# BananaSchplit-Mini-USBCPD-Schematic.net
KiCad netlist of a schematic drawn in Altium Designer
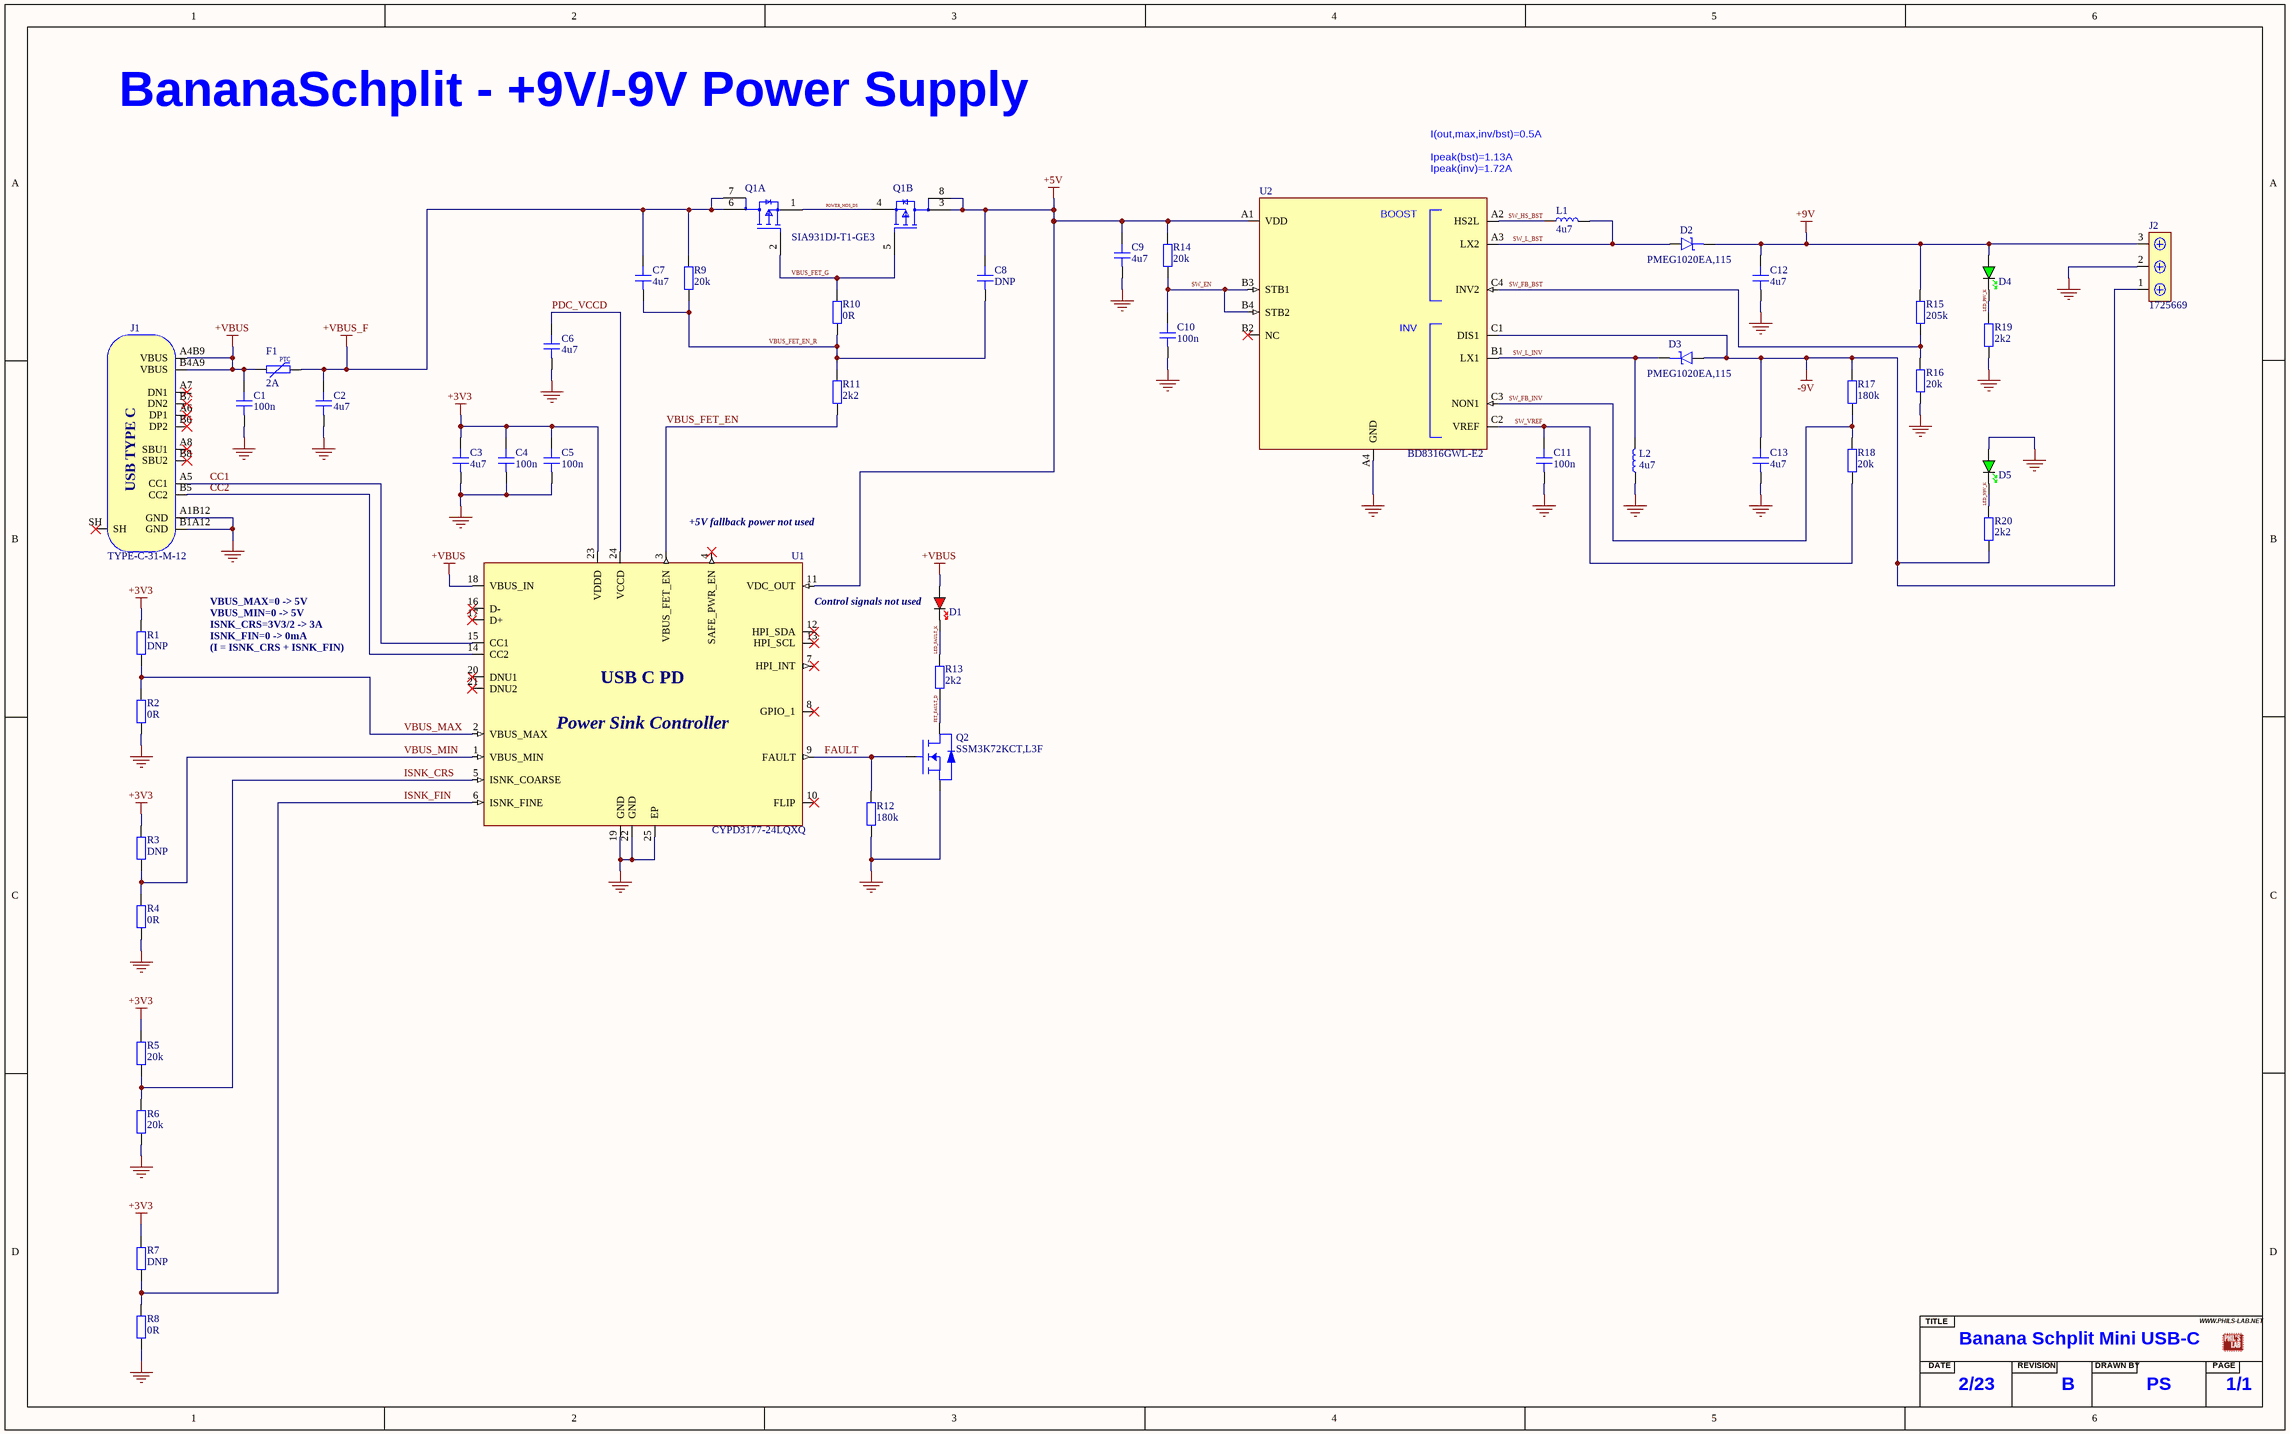
[diagram p0: BananaSchplit-Mini-USBCPD-Schematic.SchDoc]

(export (version "E")
  (design (tool "Eeschema 10.0.6"))
  (components
    (comp (ref "C1")
      (value "100n")
      (footprint "CAP_0402")
      (description "Capacitor SMD 0402 25V")
      (fields
        (field (name "MANUFACTURER") "Murata")
        (field (name "MANUFACTURER PART NUMBER") "GRM155R71H104KE14D")
      )
      (libsource (lib "Schematic-Lib-PhilsLab") (part "CAP_0402_25V"))
    )
    (comp (ref "C2")
      (value "4u7")
      (footprint "CAP_0603")
      (description "Capacitor SMD 0603 25V")
      (fields
        (field (name "MANUFACTURER") "Murata")
        (field (name "MANUFACTURER PART NUMBER") "GRT188R61E475ME13D")
      )
      (libsource (lib "Schematic-Lib-PhilsLab") (part "CAP_0603_25V"))
    )
    (comp (ref "C3")
      (value "4u7")
      (footprint "CAP_0603")
      (description "Capacitor SMD 0603 25V")
      (fields
        (field (name "MANUFACTURER") "Murata")
        (field (name "MANUFACTURER PART NUMBER") "GRT188R61E475ME13D")
      )
      (libsource (lib "Schematic-Lib-PhilsLab") (part "CAP_0603_25V"))
    )
    (comp (ref "C4")
      (value "100n")
      (footprint "CAP_0402")
      (description "Capacitor SMD 0402 25V")
      (fields
        (field (name "MANUFACTURER") "Murata")
        (field (name "MANUFACTURER PART NUMBER") "GRM155R71H104KE14D")
      )
      (libsource (lib "Schematic-Lib-PhilsLab") (part "CAP_0402_25V"))
    )
    (comp (ref "C5")
      (value "100n")
      (footprint "CAP_0402")
      (description "Capacitor SMD 0402 25V")
      (fields
        (field (name "MANUFACTURER") "Murata")
        (field (name "MANUFACTURER PART NUMBER") "GRM155R71H104KE14D")
      )
      (libsource (lib "Schematic-Lib-PhilsLab") (part "CAP_0402_25V"))
    )
    (comp (ref "C6")
      (value "4u7")
      (footprint "CAP_0603")
      (description "Capacitor SMD 0603 25V")
      (fields
        (field (name "MANUFACTURER") "Murata")
        (field (name "MANUFACTURER PART NUMBER") "GRT188R61E475ME13D")
      )
      (libsource (lib "Schematic-Lib-PhilsLab") (part "CAP_0603_25V"))
    )
    (comp (ref "C7")
      (value "4u7")
      (footprint "CAP_0603")
      (description "Capacitor SMD 0603 25V")
      (fields
        (field (name "MANUFACTURER") "Murata")
        (field (name "MANUFACTURER PART NUMBER") "GRT188R61E475ME13D")
      )
      (libsource (lib "Schematic-Lib-PhilsLab") (part "CAP_0603_25V"))
    )
    (comp (ref "C8")
      (value "DNP")
      (footprint "CAP_0402")
      (description "Capacitor SMD 0402 25V")
      (libsource (lib "Schematic-Lib-PhilsLab") (part "CAP_0402_25V"))
    )
    (comp (ref "C9")
      (value "4u7")
      (footprint "CAP_0603")
      (description "Capacitor SMD 0603 25V")
      (fields
        (field (name "MANUFACTURER") "Murata")
        (field (name "MANUFACTURER PART NUMBER") "GRT188R61E475ME13D")
      )
      (libsource (lib "Schematic-Lib-PhilsLab") (part "CAP_0603_25V"))
    )
    (comp (ref "C10")
      (value "100n")
      (footprint "CAP_0402")
      (description "Capacitor SMD 0402 25V")
      (fields
        (field (name "MANUFACTURER") "Murata")
        (field (name "MANUFACTURER PART NUMBER") "GRM155R71H104KE14D")
      )
      (libsource (lib "Schematic-Lib-PhilsLab") (part "CAP_0402_25V"))
    )
    (comp (ref "C11")
      (value "100n")
      (footprint "CAP_0402")
      (description "Capacitor SMD 0402 25V")
      (fields
        (field (name "MANUFACTURER") "Murata")
        (field (name "MANUFACTURER PART NUMBER") "GRM155R71H104KE14D")
      )
      (libsource (lib "Schematic-Lib-PhilsLab") (part "CAP_0402_25V"))
    )
    (comp (ref "C12")
      (value "4u7")
      (footprint "CAP_0603")
      (description "Capacitor SMD 0603 25V")
      (fields
        (field (name "MANUFACTURER") "Murata")
        (field (name "MANUFACTURER PART NUMBER") "GRT188R61E475ME13D")
      )
      (libsource (lib "Schematic-Lib-PhilsLab") (part "CAP_0603_25V"))
    )
    (comp (ref "C13")
      (value "4u7")
      (footprint "CAP_0603")
      (description "Capacitor SMD 0603 25V")
      (fields
        (field (name "MANUFACTURER") "Murata")
        (field (name "MANUFACTURER PART NUMBER") "GRT188R61E475ME13D")
      )
      (libsource (lib "Schematic-Lib-PhilsLab") (part "CAP_0603_25V"))
    )
    (comp (ref "D1")
      (value "RED")
      (footprint "LED_0402_RED")
      (description "LED 0402 RED SMD")
      (fields
        (field (name "MANUFACTURER") "Lite-On")
        (field (name "MANUFACTURER PART NUMBER") "LTST-C281KRKT")
      )
      (libsource (lib "Schematic-Lib-PhilsLab") (part "LED_0402_RED"))
    )
    (comp (ref "D2")
      (value "PMEG1020EA,115")
      (footprint "SOD-323")
      (description "Diode Schottky SMD SOD-323")
      (fields (field (name "MANUFACTURER") "Nexperia"))
      (libsource (lib "Schematic-Lib-PhilsLab") (part "D_SCHOTTKY_SOD_323"))
    )
    (comp (ref "D3")
      (value "PMEG1020EA,115")
      (footprint "SOD-323")
      (description "Diode Schottky SMD SOD-323")
      (fields (field (name "MANUFACTURER") "Nexperia"))
      (libsource (lib "Schematic-Lib-PhilsLab") (part "D_SCHOTTKY_SOD_323"))
    )
    (comp (ref "D4")
      (value "GREEN")
      (footprint "LED_0402_GREEN")
      (description "LED 0402 GREEN SMD")
      (fields
        (field (name "MANUFACTURER") "Lite-On")
        (field (name "MANUFACTURER PART NUMBER") "LTST-C281KGKT")
      )
      (libsource (lib "Schematic-Lib-PhilsLab") (part "LED_0402_GREEN"))
    )
    (comp (ref "D5")
      (value "GREEN")
      (footprint "LED_0402_GREEN")
      (description "LED 0402 GREEN SMD")
      (fields
        (field (name "MANUFACTURER") "Lite-On")
        (field (name "MANUFACTURER PART NUMBER") "LTST-C281KGKT")
      )
      (libsource (lib "Schematic-Lib-PhilsLab") (part "LED_0402_GREEN"))
    )
    (comp (ref "F1")
      (value "2A")
      (footprint "FUSE_1206")
      (description "Fuse PPTC SMD 1206")
      (fields (field (name "MANUFACTURER") "Eaton") (field (name "MANUFACTURER PART NUMBER") "PTS12066V200"))
      (libsource (lib "Schematic-Lib-PhilsLab") (part "FUSE_PPTC_1206"))
    )
    (comp (ref "J1")
      (value "TYPE-C-31-M-12")
      (footprint "TYPE-C-31-M-12")
      (description "USB Type C Connector Horizontal SMT")
      (fields (field (name "MANUFACTURER") "Koren Hroparts"))
      (libsource (lib "Schematic-Lib-PhilsLab") (part "TYPE-C-31-M-12"))
    )
    (comp (ref "J2")
      (value "1725669")
      (footprint "1725669")
      (description "Screw Terminal Block 3 Positions 2.54mm")
      (fields (field (name "MANUFACTURER") "Phoenix"))
      (libsource (lib "Schematic-Lib-PhilsLab") (part "1725669"))
    )
    (comp (ref "L1")
      (value "4u7")
      (footprint "SRP3212A")
      (description "Shielded Power Inductor SMD SRP3212A")
      (fields
        (field (name "MANUFACTURER") "Bourns")
        (field (name "MANUFACTURER PART NUMBER") "SRP3212A-4R7M")
      )
      (libsource (lib "Schematic-Lib-PhilsLab") (part "SRP3212A-*"))
    )
    (comp (ref "L2")
      (value "4u7")
      (footprint "SRP3212A")
      (description "Shielded Power Inductor SMD SRP3212A")
      (fields
        (field (name "MANUFACTURER") "Bourns")
        (field (name "MANUFACTURER PART NUMBER") "SRP3212A-4R7M")
      )
      (libsource (lib "Schematic-Lib-PhilsLab") (part "SRP3212A-*"))
    )
    (comp (ref "Q1")
      (value "SIA931DJ-T1-GE3")
      (footprint "FP-C-07431-DUAL-MFG")
      (description "MOSFET 2P-CH 30V 4.5A SC70-6L")
      (fields
        (field (name "MANUFACTURER") "Vishay")
        (field (name "OCTOPART") "https://octopart.com/sia931dj-t1-ge3-vishay-46488088")
      )
      (libsource (lib "Altium Content Vault") (part "000b6ffb9e5d27f556e92134adc54a4"))
    )
    (comp (ref "Q2")
      (value "SSM3K72KCT,L3F")
      (footprint "CST3-SOT-883")
      (description "MOSFET N-Channel Vds=60V Id=400mA Rds(on)=1.05R with ESD Protection")
      (fields (field (name "MANUFACTURER") "Toshiba"))
      (libsource (lib "Schematic-Lib-PhilsLab") (part "SSM3K72KCT,L3F"))
    )
    (comp (ref "R1")
      (value "DNP")
      (footprint "RES_0402")
      (description "Resistor SMD 0402")
      (libsource (lib "Schematic-Lib-PhilsLab") (part "RES_0402"))
    )
    (comp (ref "R2")
      (value "0R")
      (footprint "RES_0402")
      (description "Resistor SMD 0402")
      (fields
        (field (name "MANUFACTURER") "YAGEO")
        (field (name "MANUFACTURER PART NUMBER") "RC0402FR-070RL")
      )
      (libsource (lib "Schematic-Lib-PhilsLab") (part "RES_0402"))
    )
    (comp (ref "R3")
      (value "DNP")
      (footprint "RES_0402")
      (description "Resistor SMD 0402")
      (libsource (lib "Schematic-Lib-PhilsLab") (part "RES_0402"))
    )
    (comp (ref "R4")
      (value "0R")
      (footprint "RES_0402")
      (description "Resistor SMD 0402")
      (fields
        (field (name "MANUFACTURER") "YAGEO")
        (field (name "MANUFACTURER PART NUMBER") "RC0402FR-070RL")
      )
      (libsource (lib "Schematic-Lib-PhilsLab") (part "RES_0402"))
    )
    (comp (ref "R5")
      (value "20k")
      (footprint "RES_0402")
      (description "Resistor SMD 0402")
      (fields
        (field (name "MANUFACTURER") "YAGEO")
        (field (name "MANUFACTURER PART NUMBER") "RC0402FR-0720KL")
      )
      (libsource (lib "Schematic-Lib-PhilsLab") (part "RES_0402"))
    )
    (comp (ref "R6")
      (value "20k")
      (footprint "RES_0402")
      (description "Resistor SMD 0402")
      (fields
        (field (name "MANUFACTURER") "YAGEO")
        (field (name "MANUFACTURER PART NUMBER") "RC0402FR-0720KL")
      )
      (libsource (lib "Schematic-Lib-PhilsLab") (part "RES_0402"))
    )
    (comp (ref "R7")
      (value "DNP")
      (footprint "RES_0402")
      (description "Resistor SMD 0402")
      (libsource (lib "Schematic-Lib-PhilsLab") (part "RES_0402"))
    )
    (comp (ref "R8")
      (value "0R")
      (footprint "RES_0402")
      (description "Resistor SMD 0402")
      (fields
        (field (name "MANUFACTURER") "YAGEO")
        (field (name "MANUFACTURER PART NUMBER") "RC0402FR-070RL")
      )
      (libsource (lib "Schematic-Lib-PhilsLab") (part "RES_0402"))
    )
    (comp (ref "R9")
      (value "20k")
      (footprint "RES_0402")
      (description "Resistor SMD 0402")
      (fields
        (field (name "MANUFACTURER") "YAGEO")
        (field (name "MANUFACTURER PART NUMBER") "RC0402FR-0720KL")
      )
      (libsource (lib "Schematic-Lib-PhilsLab") (part "RES_0402"))
    )
    (comp (ref "R10")
      (value "0R")
      (footprint "RES_0402")
      (description "Resistor SMD 0402")
      (fields
        (field (name "MANUFACTURER") "YAGEO")
        (field (name "MANUFACTURER PART NUMBER") "RC0402FR-070RL")
      )
      (libsource (lib "Schematic-Lib-PhilsLab") (part "RES_0402"))
    )
    (comp (ref "R11")
      (value "2k2")
      (footprint "RES_0402")
      (description "Resistor SMD 0402")
      (fields
        (field (name "MANUFACTURER") "YAGEO")
        (field (name "MANUFACTURER PART NUMBER") "RC0402FR-072K2L")
      )
      (libsource (lib "Schematic-Lib-PhilsLab") (part "RES_0402"))
    )
    (comp (ref "R12")
      (value "180k")
      (footprint "RES_0402")
      (description "Resistor SMD 0402")
      (fields
        (field (name "MANUFACTURER") "YAGEO")
        (field (name "MANUFACTURER PART NUMBER") "RC0402FR-07180KL")
      )
      (libsource (lib "Schematic-Lib-PhilsLab") (part "RES_0402"))
    )
    (comp (ref "R13")
      (value "2k2")
      (footprint "RES_0402")
      (description "Resistor SMD 0402")
      (fields
        (field (name "MANUFACTURER") "YAGEO")
        (field (name "MANUFACTURER PART NUMBER") "RC0402FR-072K2L")
      )
      (libsource (lib "Schematic-Lib-PhilsLab") (part "RES_0402"))
    )
    (comp (ref "R14")
      (value "20k")
      (footprint "RES_0402")
      (description "Resistor SMD 0402")
      (fields
        (field (name "MANUFACTURER") "YAGEO")
        (field (name "MANUFACTURER PART NUMBER") "RC0402FR-0720KL")
      )
      (libsource (lib "Schematic-Lib-PhilsLab") (part "RES_0402"))
    )
    (comp (ref "R15")
      (value "205k")
      (footprint "RES_0402")
      (description "Resistor SMD 0402")
      (fields
        (field (name "MANUFACTURER") "YAGEO")
        (field (name "MANUFACTURER PART NUMBER") "RC0402FR-07205KL")
      )
      (libsource (lib "Schematic-Lib-PhilsLab") (part "RES_0402"))
    )
    (comp (ref "R16")
      (value "20k")
      (footprint "RES_0402")
      (description "Resistor SMD 0402")
      (fields
        (field (name "MANUFACTURER") "YAGEO")
        (field (name "MANUFACTURER PART NUMBER") "RC0402FR-0720KL")
      )
      (libsource (lib "Schematic-Lib-PhilsLab") (part "RES_0402"))
    )
    (comp (ref "R17")
      (value "180k")
      (footprint "RES_0402")
      (description "Resistor SMD 0402")
      (fields
        (field (name "MANUFACTURER") "YAGEO")
        (field (name "MANUFACTURER PART NUMBER") "RC0402FR-07180KL")
      )
      (libsource (lib "Schematic-Lib-PhilsLab") (part "RES_0402"))
    )
    (comp (ref "R18")
      (value "20k")
      (footprint "RES_0402")
      (description "Resistor SMD 0402")
      (fields
        (field (name "MANUFACTURER") "YAGEO")
        (field (name "MANUFACTURER PART NUMBER") "RC0402FR-0720KL")
      )
      (libsource (lib "Schematic-Lib-PhilsLab") (part "RES_0402"))
    )
    (comp (ref "R19")
      (value "2k2")
      (footprint "RES_0402")
      (description "Resistor SMD 0402")
      (fields
        (field (name "MANUFACTURER") "YAGEO")
        (field (name "MANUFACTURER PART NUMBER") "RC0402FR-072K2L")
      )
      (libsource (lib "Schematic-Lib-PhilsLab") (part "RES_0402"))
    )
    (comp (ref "R20")
      (value "2k2")
      (footprint "RES_0402")
      (description "Resistor SMD 0402")
      (fields
        (field (name "MANUFACTURER") "YAGEO")
        (field (name "MANUFACTURER PART NUMBER") "RC0402FR-072K2L")
      )
      (libsource (lib "Schematic-Lib-PhilsLab") (part "RES_0402"))
    )
    (comp (ref "TB")
      (value "SCHEMATIC_TITLE_BLOCK")
      (description "Default Schematic Title Block (Phil's Lab)")
      (libsource (lib "Schematic-Lib-PhilsLab") (part "SCHEMATIC_TITLE_BLOCK"))
    )
    (comp (ref "U1")
      (value "CYPD3177-24LQXQ")
      (footprint "QFN-24-0MM5")
      (description "USB Type-C Port Controller for Power Sinks")
      (fields (field (name "MANUFACTURER") "Cypress Semicon"))
      (libsource (lib "Schematic-Lib-PhilsLab") (part "CYPD3177-24LQXQ"))
    )
    (comp (ref "U2")
      (value "BD8316GWL-E2")
      (footprint "UCSP50L1")
      (description "Step-up and inverted 2-channel DC/DC converter with Built-in Power MOSFET 1.6MHz 1A")
      (fields (field (name "MANUFACTURER") "ROHM"))
      (libsource (lib "Schematic-Lib-PhilsLab") (part "BD8316GWL-E2"))
    )
  )
  (nets
    (net (code "1") (name "+3V3") (class "Default")
      (node (ref "C3") (pin "2") (pinfunction "2_2") (pintype "passive"))
      (node (ref "C4") (pin "2") (pinfunction "2_2") (pintype "passive"))
      (node (ref "C5") (pin "2") (pinfunction "2_2") (pintype "passive"))
      (node (ref "R1") (pin "2") (pinfunction "2_2") (pintype "passive"))
      (node (ref "R3") (pin "2") (pinfunction "2_2") (pintype "passive"))
      (node (ref "R5") (pin "2") (pinfunction "2_2") (pintype "passive"))
      (node (ref "R7") (pin "2") (pinfunction "2_2") (pintype "passive"))
      (node (ref "U1") (pin "23") (pinfunction "VDDD_23") (pintype "power_in"))
    )
    (net (code "2") (name "+5V") (class "Default")
      (node (ref "C8") (pin "2") (pinfunction "2_2") (pintype "passive"))
      (node (ref "C9") (pin "2") (pinfunction "2_2") (pintype "passive"))
      (node (ref "Q1") (pin "3") (pinfunction "D2_3") (pintype "passive"))
      (node (ref "Q1") (pin "8") (pinfunction "D2_8") (pintype "passive"))
      (node (ref "R14") (pin "2") (pinfunction "2_2") (pintype "passive"))
      (node (ref "U1") (pin "11") (pinfunction "VDC_OUT_11") (pintype "input"))
      (node (ref "U2") (pin "A1") (pinfunction "VDD_A1") (pintype "power_in"))
    )
    (net (code "3") (name "+9V") (class "Default")
      (node (ref "C12") (pin "2") (pinfunction "2_2") (pintype "passive"))
      (node (ref "D2") (pin "K") (pinfunction "K_K") (pintype "passive"))
      (node (ref "D4") (pin "A") (pinfunction "A_A") (pintype "passive"))
      (node (ref "J2") (pin "3") (pinfunction "3_3") (pintype "passive"))
      (node (ref "R15") (pin "2") (pinfunction "2_2") (pintype "passive"))
    )
    (net (code "4") (name "+VBUS") (class "Default")
      (node (ref "C1") (pin "2") (pinfunction "2_2") (pintype "passive"))
      (node (ref "D1") (pin "A") (pinfunction "A_A") (pintype "passive"))
      (node (ref "F1") (pin "1") (pinfunction "1_1") (pintype "passive"))
      (node (ref "J1") (pin "A4B9") (pinfunction "VBUS_A4B9") (pintype "power_in"))
      (node (ref "J1") (pin "B4A9") (pinfunction "VBUS_B4A9") (pintype "power_in"))
      (node (ref "U1") (pin "18") (pinfunction "VBUS_IN_18") (pintype "power_in"))
    )
    (net (code "5") (name "+VBUS_F") (class "Default")
      (node (ref "C2") (pin "2") (pinfunction "2_2") (pintype "passive"))
      (node (ref "C7") (pin "2") (pinfunction "2_2") (pintype "passive"))
      (node (ref "F1") (pin "2") (pinfunction "2_2") (pintype "passive"))
      (node (ref "Q1") (pin "6") (pinfunction "D1_6") (pintype "passive"))
      (node (ref "Q1") (pin "7") (pinfunction "D1_7") (pintype "passive"))
      (node (ref "R9") (pin "2") (pinfunction "2_2") (pintype "passive"))
    )
    (net (code "6") (name "-9V") (class "Default")
      (node (ref "C13") (pin "2") (pinfunction "2_2") (pintype "passive"))
      (node (ref "D3") (pin "A") (pinfunction "A_A") (pintype "passive"))
      (node (ref "J2") (pin "1") (pinfunction "1_1") (pintype "passive"))
      (node (ref "R17") (pin "2") (pinfunction "2_2") (pintype "passive"))
      (node (ref "R20") (pin "1") (pinfunction "1_1") (pintype "passive"))
      (node (ref "U2") (pin "C1") (pinfunction "DIS1_C1") (pintype "power_in"))
    )
    (net (code "7") (name "/CC1") (class "Default")
      (node (ref "J1") (pin "A5") (pinfunction "CC1_A5") (pintype "passive"))
      (node (ref "U1") (pin "15") (pinfunction "CC1_15") (pintype "bidirectional"))
    )
    (net (code "8") (name "/CC2") (class "Default")
      (node (ref "J1") (pin "B5") (pinfunction "CC2_B5") (pintype "tri_state"))
      (node (ref "U1") (pin "14") (pinfunction "CC2_14") (pintype "bidirectional"))
    )
    (net (code "9") (name "/FAULT") (class "Default")
      (node (ref "Q2") (pin "G") (pinfunction "G_G") (pintype "passive"))
      (node (ref "R12") (pin "2") (pinfunction "2_2") (pintype "passive"))
      (node (ref "U1") (pin "9") (pinfunction "FAULT_9") (pintype "output"))
    )
    (net (code "10") (name "/FET_FAULT_D") (class "Default")
      (node (ref "Q2") (pin "D") (pinfunction "D_D") (pintype "passive"))
      (node (ref "R13") (pin "1") (pinfunction "1_1") (pintype "passive"))
    )
    (net (code "11") (name "/ISNK_CRS") (class "Default")
      (node (ref "R5") (pin "1") (pinfunction "1_1") (pintype "passive"))
      (node (ref "R6") (pin "2") (pinfunction "2_2") (pintype "passive"))
      (node (ref "U1") (pin "5") (pinfunction "ISNK_COARSE_5") (pintype "input"))
    )
    (net (code "12") (name "/ISNK_FIN") (class "Default")
      (node (ref "R7") (pin "1") (pinfunction "1_1") (pintype "passive"))
      (node (ref "R8") (pin "2") (pinfunction "2_2") (pintype "passive"))
      (node (ref "U1") (pin "6") (pinfunction "ISNK_FINE_6") (pintype "input"))
    )
    (net (code "13") (name "/LED_FAULT_K") (class "Default")
      (node (ref "D1") (pin "K") (pinfunction "K_K") (pintype "passive"))
      (node (ref "R13") (pin "2") (pinfunction "2_2") (pintype "passive"))
    )
    (net (code "14") (name "/LED_N9V_K") (class "Default")
      (node (ref "D5") (pin "K") (pinfunction "K_K") (pintype "passive"))
      (node (ref "R20") (pin "2") (pinfunction "2_2") (pintype "passive"))
    )
    (net (code "15") (name "/LED_P9V_K") (class "Default")
      (node (ref "D4") (pin "K") (pinfunction "K_K") (pintype "passive"))
      (node (ref "R19") (pin "2") (pinfunction "2_2") (pintype "passive"))
    )
    (net (code "16") (name "/PDC_VCCD") (class "Default")
      (node (ref "C6") (pin "2") (pinfunction "2_2") (pintype "passive"))
      (node (ref "U1") (pin "24") (pinfunction "VCCD_24") (pintype "power_in"))
    )
    (net (code "17") (name "/POWER_MOS_DS") (class "Default")
      (node (ref "Q1") (pin "1") (pinfunction "S1_1") (pintype "passive"))
      (node (ref "Q1") (pin "4") (pinfunction "S2_4") (pintype "passive"))
    )
    (net (code "18") (name "/SW_EN") (class "Default")
      (node (ref "C10") (pin "2") (pinfunction "2_2") (pintype "passive"))
      (node (ref "R14") (pin "1") (pinfunction "1_1") (pintype "passive"))
      (node (ref "U2") (pin "B3") (pinfunction "STB1_B3") (pintype "input"))
      (node (ref "U2") (pin "B4") (pinfunction "STB2_B4") (pintype "input"))
    )
    (net (code "19") (name "/SW_FB_BST") (class "Default")
      (node (ref "R15") (pin "1") (pinfunction "1_1") (pintype "passive"))
      (node (ref "R16") (pin "2") (pinfunction "2_2") (pintype "passive"))
      (node (ref "U2") (pin "C4") (pinfunction "INV2_C4") (pintype "input"))
    )
    (net (code "20") (name "/SW_FB_INV") (class "Default")
      (node (ref "R17") (pin "1") (pinfunction "1_1") (pintype "passive"))
      (node (ref "R18") (pin "2") (pinfunction "2_2") (pintype "passive"))
      (node (ref "U2") (pin "C3") (pinfunction "NON1_C3") (pintype "input"))
    )
    (net (code "21") (name "/SW_HS_BST") (class "Default")
      (node (ref "L1") (pin "1") (pinfunction "1_1") (pintype "passive"))
      (node (ref "U2") (pin "A2") (pinfunction "HS2L_A2") (pintype "power_in"))
    )
    (net (code "22") (name "/SW_L_BST") (class "Default")
      (node (ref "D2") (pin "A") (pinfunction "A_A") (pintype "passive"))
      (node (ref "L1") (pin "2") (pinfunction "2_2") (pintype "passive"))
      (node (ref "U2") (pin "A3") (pinfunction "LX2_A3") (pintype "power_in"))
    )
    (net (code "23") (name "/SW_L_INV") (class "Default")
      (node (ref "D3") (pin "K") (pinfunction "K_K") (pintype "passive"))
      (node (ref "L2") (pin "2") (pinfunction "2_2") (pintype "passive"))
      (node (ref "U2") (pin "B1") (pinfunction "LX1_B1") (pintype "power_in"))
    )
    (net (code "24") (name "/SW_VREF") (class "Default")
      (node (ref "C11") (pin "2") (pinfunction "2_2") (pintype "passive"))
      (node (ref "R18") (pin "1") (pinfunction "1_1") (pintype "passive"))
      (node (ref "U2") (pin "C2") (pinfunction "VREF_C2") (pintype "power_in"))
    )
    (net (code "25") (name "/VBUS_FET_EN") (class "Default")
      (node (ref "R11") (pin "1") (pinfunction "1_1") (pintype "passive"))
      (node (ref "U1") (pin "3") (pinfunction "VBUS_FET_EN_3") (pintype "output"))
    )
    (net (code "26") (name "/VBUS_FET_EN_R") (class "Default")
      (node (ref "C7") (pin "1") (pinfunction "1_1") (pintype "passive"))
      (node (ref "C8") (pin "1") (pinfunction "1_1") (pintype "passive"))
      (node (ref "R10") (pin "1") (pinfunction "1_1") (pintype "passive"))
      (node (ref "R11") (pin "2") (pinfunction "2_2") (pintype "passive"))
      (node (ref "R9") (pin "1") (pinfunction "1_1") (pintype "passive"))
    )
    (net (code "27") (name "/VBUS_FET_G") (class "Default")
      (node (ref "Q1") (pin "2") (pinfunction "G1_2") (pintype "passive"))
      (node (ref "Q1") (pin "5") (pinfunction "G2_5") (pintype "passive"))
      (node (ref "R10") (pin "2") (pinfunction "2_2") (pintype "passive"))
    )
    (net (code "28") (name "/VBUS_MAX") (class "Default")
      (node (ref "R1") (pin "1") (pinfunction "1_1") (pintype "passive"))
      (node (ref "R2") (pin "2") (pinfunction "2_2") (pintype "passive"))
      (node (ref "U1") (pin "2") (pinfunction "VBUS_MAX_2") (pintype "input"))
    )
    (net (code "29") (name "/VBUS_MIN") (class "Default")
      (node (ref "R3") (pin "1") (pinfunction "1_1") (pintype "passive"))
      (node (ref "R4") (pin "2") (pinfunction "2_2") (pintype "passive"))
      (node (ref "U1") (pin "1") (pinfunction "VBUS_MIN_1") (pintype "input"))
    )
    (net (code "30") (name "GND") (class "Default")
      (node (ref "C1") (pin "1") (pinfunction "1_1") (pintype "passive"))
      (node (ref "C10") (pin "1") (pinfunction "1_1") (pintype "passive"))
      (node (ref "C11") (pin "1") (pinfunction "1_1") (pintype "passive"))
      (node (ref "C12") (pin "1") (pinfunction "1_1") (pintype "passive"))
      (node (ref "C13") (pin "1") (pinfunction "1_1") (pintype "passive"))
      (node (ref "C2") (pin "1") (pinfunction "1_1") (pintype "passive"))
      (node (ref "C3") (pin "1") (pinfunction "1_1") (pintype "passive"))
      (node (ref "C4") (pin "1") (pinfunction "1_1") (pintype "passive"))
      (node (ref "C5") (pin "1") (pinfunction "1_1") (pintype "passive"))
      (node (ref "C6") (pin "1") (pinfunction "1_1") (pintype "passive"))
      (node (ref "C9") (pin "1") (pinfunction "1_1") (pintype "passive"))
      (node (ref "D5") (pin "A") (pinfunction "A_A") (pintype "passive"))
      (node (ref "J1") (pin "A1B12") (pinfunction "GND_A1B12") (pintype "power_in"))
      (node (ref "J1") (pin "B1A12") (pinfunction "GND_B1A12") (pintype "power_in"))
      (node (ref "J2") (pin "2") (pinfunction "2_2") (pintype "passive"))
      (node (ref "L2") (pin "1") (pinfunction "1_1") (pintype "passive"))
      (node (ref "Q2") (pin "S") (pinfunction "S_S") (pintype "passive"))
      (node (ref "R12") (pin "1") (pinfunction "1_1") (pintype "passive"))
      (node (ref "R16") (pin "1") (pinfunction "1_1") (pintype "passive"))
      (node (ref "R19") (pin "1") (pinfunction "1_1") (pintype "passive"))
      (node (ref "R2") (pin "1") (pinfunction "1_1") (pintype "passive"))
      (node (ref "R4") (pin "1") (pinfunction "1_1") (pintype "passive"))
      (node (ref "R6") (pin "1") (pinfunction "1_1") (pintype "passive"))
      (node (ref "R8") (pin "1") (pinfunction "1_1") (pintype "passive"))
      (node (ref "U1") (pin "19") (pinfunction "GND_19") (pintype "power_in"))
      (node (ref "U1") (pin "22") (pinfunction "GND_22") (pintype "power_in"))
      (node (ref "U1") (pin "25") (pinfunction "EP_25") (pintype "power_in"))
      (node (ref "U2") (pin "A4") (pinfunction "GND_A4") (pintype "power_in"))
    )
    (net (code "31") (name "unconnected-(J1-DN1-PadA7)") (class "Default")
      (node (ref "J1") (pin "A7") (pinfunction "DN1_A7") (pintype "bidirectional+no_connect"))
    )
    (net (code "32") (name "unconnected-(J1-DN2-PadB7)") (class "Default")
      (node (ref "J1") (pin "B7") (pinfunction "DN2_B7") (pintype "bidirectional+no_connect"))
    )
    (net (code "33") (name "unconnected-(J1-DP1-PadA6)") (class "Default")
      (node (ref "J1") (pin "A6") (pinfunction "DP1_A6") (pintype "bidirectional+no_connect"))
    )
    (net (code "34") (name "unconnected-(J1-DP2-PadB6)") (class "Default")
      (node (ref "J1") (pin "B6") (pinfunction "DP2_B6") (pintype "bidirectional+no_connect"))
    )
    (net (code "35") (name "unconnected-(J1-PadSH)") (class "Default")
      (node (ref "J1") (pin "SH") (pinfunction "SH_SH") (pintype "power_in+no_connect"))
    )
    (net (code "36") (name "unconnected-(J1-SBU1-PadA8)") (class "Default")
      (node (ref "J1") (pin "A8") (pinfunction "SBU1_A8") (pintype "bidirectional+no_connect"))
    )
    (net (code "37") (name "unconnected-(J1-SBU2-PadB8)") (class "Default")
      (node (ref "J1") (pin "B8") (pinfunction "SBU2_B8") (pintype "bidirectional+no_connect"))
    )
    (net (code "38") (name "unconnected-(U1-D+-Pad17)") (class "Default")
      (node (ref "U1") (pin "17") (pinfunction "D+_17") (pintype "passive+no_connect"))
    )
    (net (code "39") (name "unconnected-(U1-D--Pad16)") (class "Default")
      (node (ref "U1") (pin "16") (pinfunction "D-_16") (pintype "passive+no_connect"))
    )
    (net (code "40") (name "unconnected-(U1-DNU1-Pad20)") (class "Default")
      (node (ref "U1") (pin "20") (pinfunction "DNU1_20") (pintype "passive+no_connect"))
    )
    (net (code "41") (name "unconnected-(U1-DNU2-Pad21)") (class "Default")
      (node (ref "U1") (pin "21") (pinfunction "DNU2_21") (pintype "passive+no_connect"))
    )
    (net (code "42") (name "unconnected-(U1-FLIP-Pad10)") (class "Default")
      (node (ref "U1") (pin "10") (pinfunction "FLIP_10") (pintype "open_collector+no_connect"))
    )
    (net (code "43") (name "unconnected-(U1-GPIO_1-Pad8)") (class "Default")
      (node (ref "U1") (pin "8") (pinfunction "GPIO_1_8") (pintype "bidirectional+no_connect"))
    )
    (net (code "44") (name "unconnected-(U1-HPI_INT-Pad7)") (class "Default")
      (node (ref "U1") (pin "7") (pinfunction "HPI_INT_7") (pintype "output+no_connect"))
    )
    (net (code "45") (name "unconnected-(U1-HPI_SCL-Pad13)") (class "Default")
      (node (ref "U1") (pin "13") (pinfunction "HPI_SCL_13") (pintype "open_collector+no_connect"))
    )
    (net (code "46") (name "unconnected-(U1-HPI_SDA-Pad12)") (class "Default")
      (node (ref "U1") (pin "12") (pinfunction "HPI_SDA_12") (pintype "open_collector+no_connect"))
    )
    (net (code "47") (name "unconnected-(U1-SAFE_PWR_EN-Pad4)") (class "Default")
      (node (ref "U1") (pin "4") (pinfunction "SAFE_PWR_EN_4") (pintype "output+no_connect"))
    )
    (net (code "48") (name "unconnected-(U2-NC-PadB2)") (class "Default")
      (node (ref "U2") (pin "B2") (pinfunction "NC_B2") (pintype "passive+no_connect"))
    )
  )
)
